# ir2184_smd.net
KiCad netlist of a schematic drawn in EAGLE
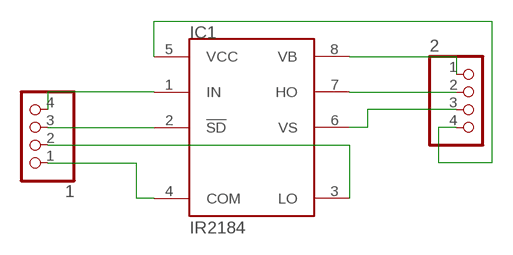
[diagram p0: schematic, sheet 1]

(export (version "E")
  (design (tool "Eeschema 10.0.6"))
  (components
    (comp (ref "1")
      (value "PINHD-1X4")
      (footprint "eagle-import:1X04")
      (libsource (lib "eagle-import") (part "PINHD-1X4"))
    )
    (comp (ref "2")
      (value "PINHD-1X4")
      (footprint "eagle-import:1X04")
      (libsource (lib "eagle-import") (part "PINHD-1X4"))
    )
    (comp (ref "IC1")
      (value "IR2184")
      (footprint "eagle-import:SO08")
      (libsource (lib "eagle-import") (part "IR2184"))
    )
  )
  (nets
    (net (code "1") (name "Net-(IC1-COM)") (class "Default")
      (node (ref "1") (pin "1") (pinfunction "1_1") (pintype "passive"))
      (node (ref "IC1") (pin "4") (pinfunction "COM_4") (pintype "power_in"))
    )
    (net (code "2") (name "Net-(IC1-HO)") (class "Default")
      (node (ref "2") (pin "2") (pinfunction "2_2") (pintype "passive"))
      (node (ref "IC1") (pin "7") (pinfunction "HO_7") (pintype "output"))
    )
    (net (code "3") (name "Net-(IC1-IN)") (class "Default")
      (node (ref "1") (pin "4") (pinfunction "4_4") (pintype "passive"))
      (node (ref "IC1") (pin "1") (pinfunction "IN_1") (pintype "input"))
    )
    (net (code "4") (name "Net-(IC1-LO)") (class "Default")
      (node (ref "1") (pin "2") (pinfunction "2_2") (pintype "passive"))
      (node (ref "IC1") (pin "3") (pinfunction "LO_3") (pintype "output"))
    )
    (net (code "5") (name "Net-(IC1-VB)") (class "Default")
      (node (ref "2") (pin "1") (pinfunction "1_1") (pintype "passive"))
      (node (ref "IC1") (pin "8") (pinfunction "VB_8") (pintype "power_in"))
    )
    (net (code "6") (name "Net-(IC1-VCC)") (class "Default")
      (node (ref "2") (pin "4") (pinfunction "4_4") (pintype "passive"))
      (node (ref "IC1") (pin "5") (pinfunction "VCC_5") (pintype "power_in"))
    )
    (net (code "7") (name "Net-(IC1-VS)") (class "Default")
      (node (ref "2") (pin "3") (pinfunction "3_3") (pintype "passive"))
      (node (ref "IC1") (pin "6") (pinfunction "VS_6") (pintype "power_in"))
    )
    (net (code "8") (name "Net-(IC1-~{SD})") (class "Default")
      (node (ref "1") (pin "3") (pinfunction "3_3") (pintype "passive"))
      (node (ref "IC1") (pin "2") (pinfunction "~{SD}_2") (pintype "input"))
    )
  )
)
